# ActiTouch_Receiver_Sheet1.net
KiCad netlist of a schematic drawn in Altium Designer
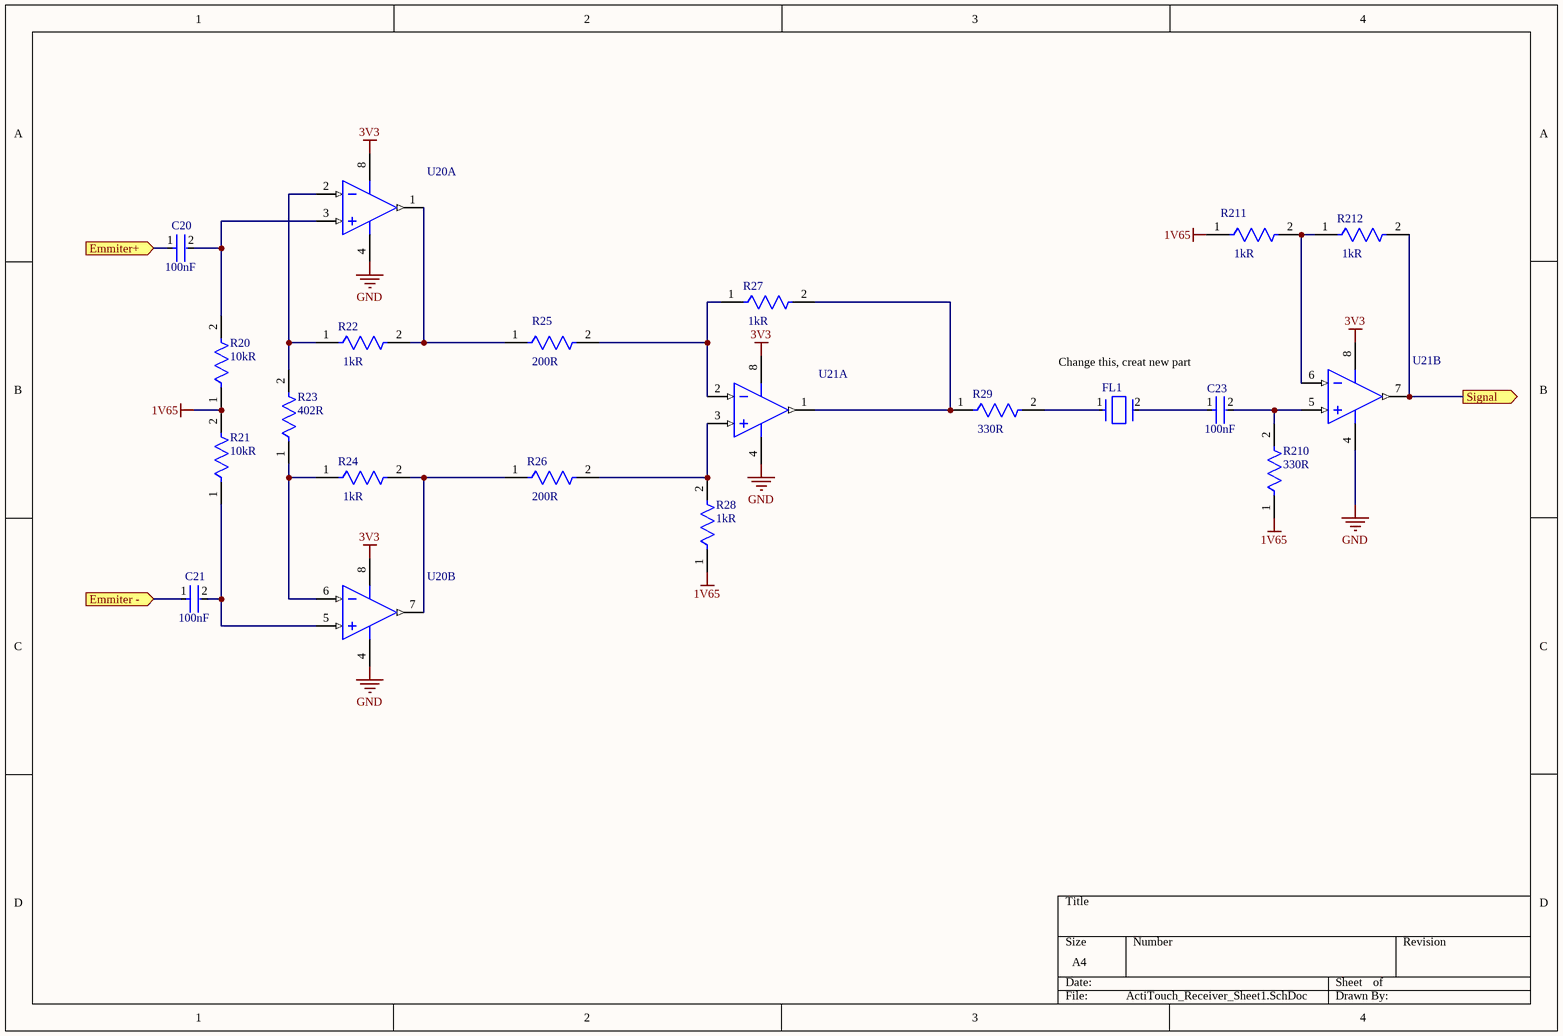
[diagram p0: ActiTouch_Receiver_Sheet1.SchDoc]

(export (version "E")
  (design (tool "Eeschema 10.0.6"))
  (components
    (comp (ref "C20")
      (value "EMK107B7104KAHT")
      (footprint "FP-0603-L_1_6_0_1-W_0_8_0-IPC_B")
      (description "None")
      (fields (field (name "CAPACITANCE") "100nF") (field (name "TOLERANCE") "10%"))
      (libsource (lib "Altium Content Vault") (part "02cd4be3c70576c341d710602a673aa"))
    )
    (comp (ref "C21")
      (value "EMK107B7104KAHT")
      (footprint "FP-0603-L_1_6_0_1-W_0_8_0-IPC_B")
      (description "None")
      (fields (field (name "CAPACITANCE") "100nF") (field (name "TOLERANCE") "10%"))
      (libsource (lib "Altium Content Vault") (part "02cd4be3c70576c341d710602a673aa"))
    )
    (comp (ref "C23")
      (value "EMK107B7104KAHT")
      (footprint "FP-0603-L_1_6_0_1-W_0_8_0-IPC_B")
      (description "None")
      (fields (field (name "CAPACITANCE") "100nF") (field (name "TOLERANCE") "10%"))
      (libsource (lib "Altium Content Vault") (part "02cd4be3c70576c341d710602a673aa"))
    )
    (comp (ref "FL1")
      (value "CDSCB10M7GA121-R0")
      (footprint "FP-CDSCB10M7GA121-R0-MFG")
      (description "Ceramic Filter 10.7MHz 2-Pin Surface Mount Emboss T/R")
      (libsource (lib "Altium Content Vault") (part "c23a69dc6c9e2f18f2079038eb95dd1"))
    )
    (comp (ref "R20")
      (value "RNCP0603FTD10R0")
      (footprint "FP-RNCP0603-MFG")
      (description "10Ω ±1% 0.125W 0603 High Power Anti-Sulfur Thin Film Chip Resistor")
      (fields (field (name "TOLERANCE") "1%") (field (name "RESISTANCE") "10kR"))
      (libsource (lib "Altium Content Vault") (part "1029c3af85768c4190bb7ad29bc67b5"))
    )
    (comp (ref "R21")
      (value "RNCP0603FTD10R0")
      (footprint "FP-RNCP0603-MFG")
      (description "10Ω ±1% 0.125W 0603 High Power Anti-Sulfur Thin Film Chip Resistor")
      (fields (field (name "TOLERANCE") "1%") (field (name "RESISTANCE") "10kR"))
      (libsource (lib "Altium Content Vault") (part "1029c3af85768c4190bb7ad29bc67b5"))
    )
    (comp (ref "R22")
      (value "RNCP0603FTD10R0")
      (footprint "FP-RNCP0603-MFG")
      (description "10Ω ±1% 0.125W 0603 High Power Anti-Sulfur Thin Film Chip Resistor")
      (fields (field (name "TOLERANCE") "1%") (field (name "RESISTANCE") "1kR"))
      (libsource (lib "Altium Content Vault") (part "1029c3af85768c4190bb7ad29bc67b5"))
    )
    (comp (ref "R23")
      (value "RNCP0603FTD10R0")
      (footprint "FP-RNCP0603-MFG")
      (description "10Ω ±1% 0.125W 0603 High Power Anti-Sulfur Thin Film Chip Resistor")
      (fields (field (name "TOLERANCE") "1%") (field (name "RESISTANCE") "402R"))
      (libsource (lib "Altium Content Vault") (part "1029c3af85768c4190bb7ad29bc67b5"))
    )
    (comp (ref "R24")
      (value "RNCP0603FTD10R0")
      (footprint "FP-RNCP0603-MFG")
      (description "10Ω ±1% 0.125W 0603 High Power Anti-Sulfur Thin Film Chip Resistor")
      (fields (field (name "TOLERANCE") "1%") (field (name "RESISTANCE") "1kR"))
      (libsource (lib "Altium Content Vault") (part "1029c3af85768c4190bb7ad29bc67b5"))
    )
    (comp (ref "R25")
      (value "RNCP0603FTD10R0")
      (footprint "FP-RNCP0603-MFG")
      (description "10Ω ±1% 0.125W 0603 High Power Anti-Sulfur Thin Film Chip Resistor")
      (fields (field (name "TOLERANCE") "1%") (field (name "RESISTANCE") "200R"))
      (libsource (lib "Altium Content Vault") (part "1029c3af85768c4190bb7ad29bc67b5"))
    )
    (comp (ref "R26")
      (value "RNCP0603FTD10R0")
      (footprint "FP-RNCP0603-MFG")
      (description "10Ω ±1% 0.125W 0603 High Power Anti-Sulfur Thin Film Chip Resistor")
      (fields (field (name "TOLERANCE") "1%") (field (name "RESISTANCE") "200R"))
      (libsource (lib "Altium Content Vault") (part "1029c3af85768c4190bb7ad29bc67b5"))
    )
    (comp (ref "R27")
      (value "RNCP0603FTD10R0")
      (footprint "FP-RNCP0603-MFG")
      (description "10Ω ±1% 0.125W 0603 High Power Anti-Sulfur Thin Film Chip Resistor")
      (fields (field (name "TOLERANCE") "1%") (field (name "RESISTANCE") "1kR"))
      (libsource (lib "Altium Content Vault") (part "1029c3af85768c4190bb7ad29bc67b5"))
    )
    (comp (ref "R28")
      (value "RNCP0603FTD10R0")
      (footprint "FP-RNCP0603-MFG")
      (description "10Ω ±1% 0.125W 0603 High Power Anti-Sulfur Thin Film Chip Resistor")
      (fields (field (name "TOLERANCE") "1%") (field (name "RESISTANCE") "1kR"))
      (libsource (lib "Altium Content Vault") (part "1029c3af85768c4190bb7ad29bc67b5"))
    )
    (comp (ref "R29")
      (value "RNCP0603FTD10R0")
      (footprint "FP-RNCP0603-MFG")
      (description "10Ω ±1% 0.125W 0603 High Power Anti-Sulfur Thin Film Chip Resistor")
      (fields (field (name "TOLERANCE") "1%") (field (name "RESISTANCE") "330R"))
      (libsource (lib "Altium Content Vault") (part "1029c3af85768c4190bb7ad29bc67b5"))
    )
    (comp (ref "R210")
      (value "RNCP0603FTD10R0")
      (footprint "FP-RNCP0603-MFG")
      (description "10Ω ±1% 0.125W 0603 High Power Anti-Sulfur Thin Film Chip Resistor")
      (fields (field (name "TOLERANCE") "1%") (field (name "RESISTANCE") "330R"))
      (libsource (lib "Altium Content Vault") (part "1029c3af85768c4190bb7ad29bc67b5"))
    )
    (comp (ref "R211")
      (value "RNCP0603FTD10R0")
      (footprint "FP-RNCP0603-MFG")
      (description "10Ω ±1% 0.125W 0603 High Power Anti-Sulfur Thin Film Chip Resistor")
      (fields (field (name "TOLERANCE") "1%") (field (name "RESISTANCE") "1kR"))
      (libsource (lib "Altium Content Vault") (part "1029c3af85768c4190bb7ad29bc67b5"))
    )
    (comp (ref "R212")
      (value "RNCP0603FTD10R0")
      (footprint "FP-RNCP0603-MFG")
      (description "10Ω ±1% 0.125W 0603 High Power Anti-Sulfur Thin Film Chip Resistor")
      (fields (field (name "TOLERANCE") "1%") (field (name "RESISTANCE") "1kR"))
      (libsource (lib "Altium Content Vault") (part "1029c3af85768c4190bb7ad29bc67b5"))
    )
    (comp (ref "U20")
      (value "OPA2836IDR")
      (footprint "D0008A_M")
      (fields (field (name "MANUFACTURER") "Texas Instruments"))
      (libsource (lib "Altium Content Vault") (part "TI-OPA2836D8"))
    )
    (comp (ref "U21")
      (value "OPA2836IDR")
      (footprint "D0008A_M")
      (fields (field (name "MANUFACTURER") "Texas Instruments"))
      (libsource (lib "Altium Content Vault") (part "TI-OPA2836D8"))
    )
  )
  (nets
    (net (code "1") (name "/Emmiter -") (class "Default")
      (node (ref "C21") (pin "1") (pinfunction "1_1") (pintype "passive"))
    )
    (net (code "2") (name "/Emmiter+") (class "Default")
      (node (ref "C20") (pin "1") (pinfunction "1_1") (pintype "passive"))
    )
    (net (code "3") (name "/Signal") (class "Default")
      (node (ref "R212") (pin "2") (pinfunction "2_2") (pintype "passive"))
      (node (ref "U21") (pin "7") (pinfunction "VOUT2_7") (pintype "output"))
    )
    (net (code "4") (name "1V65") (class "Default")
      (node (ref "R20") (pin "1") (pinfunction "1_1") (pintype "passive"))
      (node (ref "R21") (pin "2") (pinfunction "2_2") (pintype "passive"))
      (node (ref "R210") (pin "1") (pinfunction "1_1") (pintype "passive"))
      (node (ref "R211") (pin "1") (pinfunction "1_1") (pintype "passive"))
      (node (ref "R28") (pin "1") (pinfunction "1_1") (pintype "passive"))
    )
    (net (code "5") (name "3V3") (class "Default")
      (node (ref "U20") (pin "8") (pinfunction "VS+_8") (pintype "power_in"))
      (node (ref "U21") (pin "8") (pinfunction "VS+_8") (pintype "power_in"))
    )
    (net (code "6") (name "GND") (class "Default")
      (node (ref "U20") (pin "4") (pinfunction "VS-_4") (pintype "power_in"))
      (node (ref "U21") (pin "4") (pinfunction "VS-_4") (pintype "power_in"))
    )
    (net (code "7") (name "Net-(C23-Pad1)") (class "Default")
      (node (ref "C23") (pin "1") (pinfunction "1_1") (pintype "passive"))
      (node (ref "FL1") (pin "2") (pinfunction "2_2") (pintype "passive"))
    )
    (net (code "8") (name "Net-(FL1-Pad1)") (class "Default")
      (node (ref "FL1") (pin "1") (pinfunction "1_1") (pintype "passive"))
      (node (ref "R29") (pin "2") (pinfunction "2_2") (pintype "passive"))
    )
    (net (code "9") (name "Net-(U20A-VIN1+)") (class "Default")
      (node (ref "C20") (pin "2") (pinfunction "2_2") (pintype "passive"))
      (node (ref "R20") (pin "2") (pinfunction "2_2") (pintype "passive"))
      (node (ref "U20") (pin "3") (pinfunction "VIN1+_3") (pintype "input"))
    )
    (net (code "10") (name "Net-(U20A-VIN1-)") (class "Default")
      (node (ref "R22") (pin "1") (pinfunction "1_1") (pintype "passive"))
      (node (ref "R23") (pin "2") (pinfunction "2_2") (pintype "passive"))
      (node (ref "U20") (pin "2") (pinfunction "VIN1-_2") (pintype "input"))
    )
    (net (code "11") (name "Net-(U20A-VOUT1)") (class "Default")
      (node (ref "R22") (pin "2") (pinfunction "2_2") (pintype "passive"))
      (node (ref "R25") (pin "1") (pinfunction "1_1") (pintype "passive"))
      (node (ref "U20") (pin "1") (pinfunction "VOUT1_1") (pintype "output"))
    )
    (net (code "12") (name "Net-(U20B-VIN2+)") (class "Default")
      (node (ref "C21") (pin "2") (pinfunction "2_2") (pintype "passive"))
      (node (ref "R21") (pin "1") (pinfunction "1_1") (pintype "passive"))
      (node (ref "U20") (pin "5") (pinfunction "VIN2+_5") (pintype "input"))
    )
    (net (code "13") (name "Net-(U20B-VIN2-)") (class "Default")
      (node (ref "R23") (pin "1") (pinfunction "1_1") (pintype "passive"))
      (node (ref "R24") (pin "1") (pinfunction "1_1") (pintype "passive"))
      (node (ref "U20") (pin "6") (pinfunction "VIN2-_6") (pintype "input"))
    )
    (net (code "14") (name "Net-(U20B-VOUT2)") (class "Default")
      (node (ref "R24") (pin "2") (pinfunction "2_2") (pintype "passive"))
      (node (ref "R26") (pin "1") (pinfunction "1_1") (pintype "passive"))
      (node (ref "U20") (pin "7") (pinfunction "VOUT2_7") (pintype "output"))
    )
    (net (code "15") (name "Net-(U21A-VIN1+)") (class "Default")
      (node (ref "R26") (pin "2") (pinfunction "2_2") (pintype "passive"))
      (node (ref "R28") (pin "2") (pinfunction "2_2") (pintype "passive"))
      (node (ref "U21") (pin "3") (pinfunction "VIN1+_3") (pintype "input"))
    )
    (net (code "16") (name "Net-(U21A-VIN1-)") (class "Default")
      (node (ref "R25") (pin "2") (pinfunction "2_2") (pintype "passive"))
      (node (ref "R27") (pin "1") (pinfunction "1_1") (pintype "passive"))
      (node (ref "U21") (pin "2") (pinfunction "VIN1-_2") (pintype "input"))
    )
    (net (code "17") (name "Net-(U21A-VOUT1)") (class "Default")
      (node (ref "R27") (pin "2") (pinfunction "2_2") (pintype "passive"))
      (node (ref "R29") (pin "1") (pinfunction "1_1") (pintype "passive"))
      (node (ref "U21") (pin "1") (pinfunction "VOUT1_1") (pintype "output"))
    )
    (net (code "18") (name "Net-(U21B-VIN2+)") (class "Default")
      (node (ref "C23") (pin "2") (pinfunction "2_2") (pintype "passive"))
      (node (ref "R210") (pin "2") (pinfunction "2_2") (pintype "passive"))
      (node (ref "U21") (pin "5") (pinfunction "VIN2+_5") (pintype "input"))
    )
    (net (code "19") (name "Net-(U21B-VIN2-)") (class "Default")
      (node (ref "R211") (pin "2") (pinfunction "2_2") (pintype "passive"))
      (node (ref "R212") (pin "1") (pinfunction "1_1") (pintype "passive"))
      (node (ref "U21") (pin "6") (pinfunction "VIN2-_6") (pintype "input"))
    )
  )
)
